# SFP.net
KiCad netlist of a schematic drawn in Altium Designer
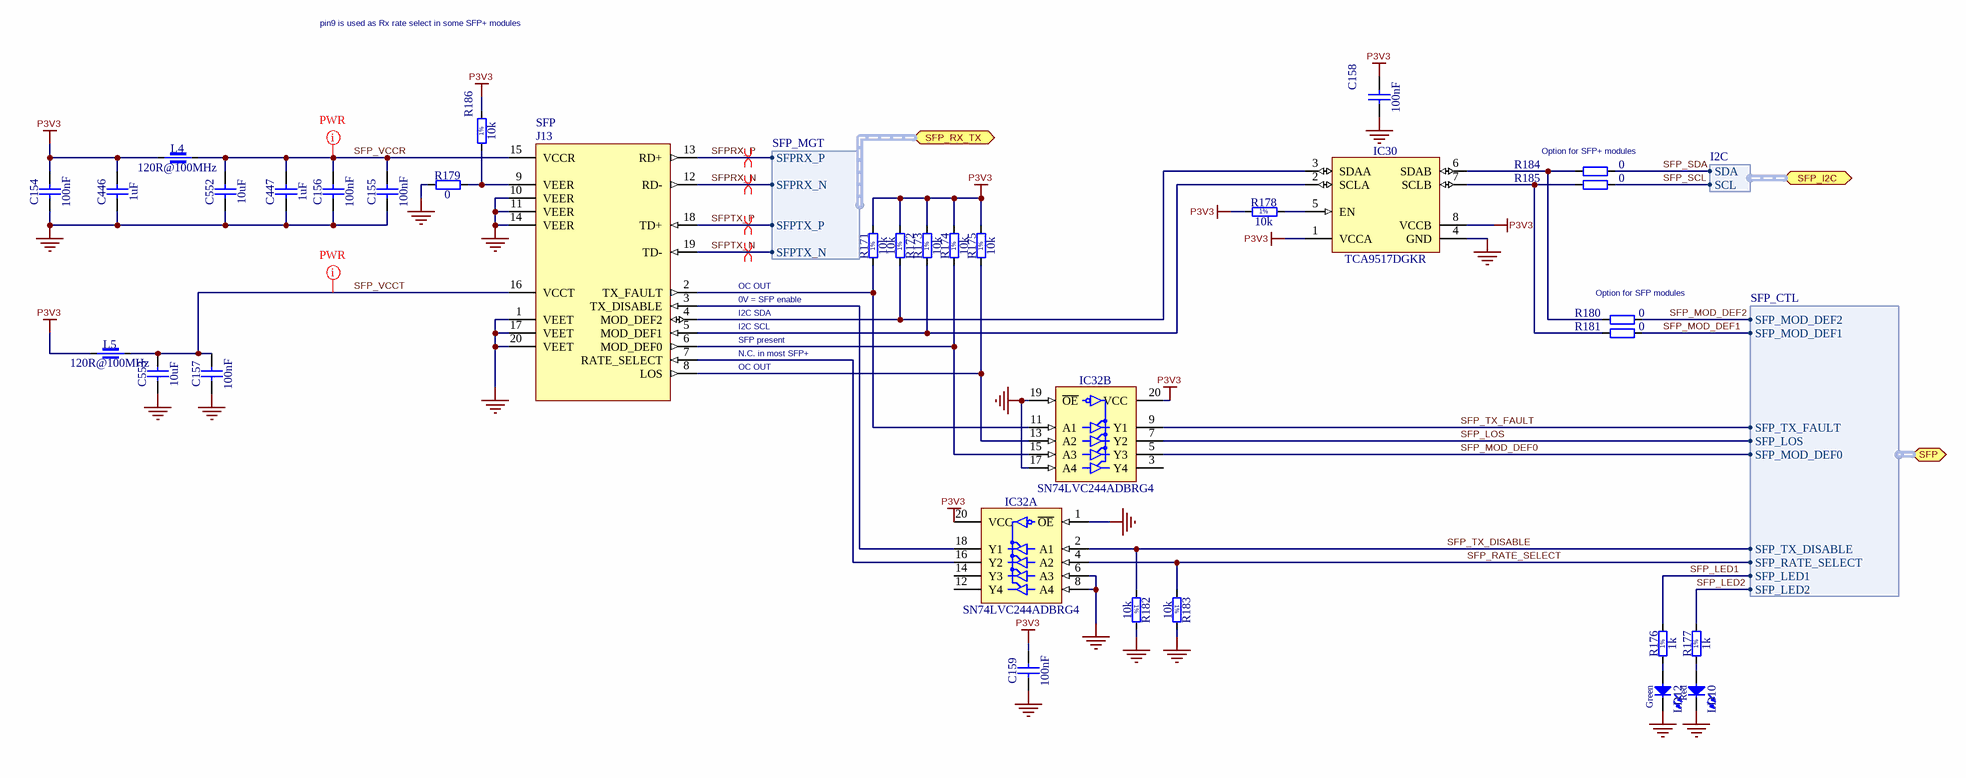
[diagram p0: SFP.SchDoc]

(export (version "E")
  (design (tool "Eeschema 10.0.6"))
  (components
    (comp (ref "C154")
      (value "100nF")
      (footprint "CAPC0603X33N")
      (description "Non-polarised capacitor")
      (fields
        (field (name "MANUFACTURER PART NUMBER") "CC0201_100NF_6.3V_10%_X5R")
        (field (name "MANUFACTURER") "GENERIC")
        (field (name "AUTHOR") "CERN DEM JLC")
      )
      (libsource (lib "Capacitors") (part "Capacitor - non polarized"))
    )
    (comp (ref "C155")
      (value "100nF")
      (footprint "CAPC0603X33N")
      (description "Non-polarised capacitor")
      (fields
        (field (name "MANUFACTURER PART NUMBER") "CC0201_100NF_6.3V_10%_X5R")
        (field (name "MANUFACTURER") "GENERIC")
        (field (name "AUTHOR") "CERN DEM JLC")
      )
      (libsource (lib "Capacitors") (part "Capacitor - non polarized"))
    )
    (comp (ref "C156")
      (value "100nF")
      (footprint "CAPC0603X33N")
      (description "Non-polarised capacitor")
      (fields
        (field (name "MANUFACTURER PART NUMBER") "CC0201_100NF_6.3V_10%_X5R")
        (field (name "MANUFACTURER") "GENERIC")
        (field (name "AUTHOR") "CERN DEM JLC")
      )
      (libsource (lib "Capacitors") (part "Capacitor - non polarized"))
    )
    (comp (ref "C157")
      (value "100nF")
      (footprint "CAPC0603X33N")
      (description "Non-polarised capacitor")
      (fields
        (field (name "MANUFACTURER PART NUMBER") "CC0201_100NF_6.3V_10%_X5R")
        (field (name "MANUFACTURER") "GENERIC")
        (field (name "AUTHOR") "CERN DEM JLC")
      )
      (libsource (lib "Capacitors") (part "Capacitor - non polarized"))
    )
    (comp (ref "C158")
      (value "100nF")
      (footprint "CAPC0603X33N")
      (description "Non-polarised capacitor")
      (fields
        (field (name "MANUFACTURER PART NUMBER") "CC0201_100NF_6.3V_10%_X5R")
        (field (name "MANUFACTURER") "GENERIC")
        (field (name "AUTHOR") "CERN DEM JLC")
      )
      (libsource (lib "Capacitors") (part "Capacitor - non polarized"))
    )
    (comp (ref "C159")
      (value "100nF")
      (footprint "CAPC0603X33N")
      (description "Non-polarised capacitor")
      (fields
        (field (name "MANUFACTURER PART NUMBER") "CC0201_100NF_6.3V_10%_X5R")
        (field (name "MANUFACTURER") "GENERIC")
        (field (name "AUTHOR") "CERN DEM JLC")
      )
      (libsource (lib "Capacitors") (part "Capacitor - non polarized"))
    )
    (comp (ref "C446")
      (value "1uF")
      (footprint "CAPC1005X55N")
      (description "Non-polarised capacitor")
      (fields
        (field (name "MANUFACTURER PART NUMBER") "CC0402_1UF_16V_10%_X5R")
        (field (name "MANUFACTURER") "GENERIC")
        (field (name "AUTHOR") "CERN DEM JLC")
      )
      (libsource (lib "Capacitors") (part "Capacitor - non polarized"))
    )
    (comp (ref "C447")
      (value "1uF")
      (footprint "CAPC1005X55N")
      (description "Non-polarised capacitor")
      (fields
        (field (name "MANUFACTURER PART NUMBER") "CC0402_1UF_16V_10%_X5R")
        (field (name "MANUFACTURER") "GENERIC")
        (field (name "AUTHOR") "CERN DEM JLC")
      )
      (libsource (lib "Capacitors") (part "Capacitor - non polarized"))
    )
    (comp (ref "C552")
      (value "10uF")
      (footprint "CAPC1608X87N")
      (description "Non-polarised capacitor")
      (fields
        (field (name "MANUFACTURER PART NUMBER") "CC0603_10uF_6.3V_20%_X5R")
        (field (name "MANUFACTURER") "GENERIC")
        (field (name "AUTHOR") "CERN DEM JLC")
      )
      (libsource (lib "Capacitors") (part "Capacitor - non polarized"))
    )
    (comp (ref "C553")
      (value "10uF")
      (footprint "CAPC1608X87N")
      (description "Non-polarised capacitor")
      (fields
        (field (name "MANUFACTURER PART NUMBER") "CC0603_10uF_6.3V_20%_X5R")
        (field (name "MANUFACTURER") "GENERIC")
        (field (name "AUTHOR") "CERN DEM JLC")
      )
      (libsource (lib "Capacitors") (part "Capacitor - non polarized"))
    )
    (comp (ref "IC30")
      (value "TCA9517DGKR")
      (footprint "SOP65P490X110-8N")
      (description "Level-Translating I2C Bus Repeater")
      (fields (field (name "MANUFACTURER") "TEXAS INSTRUMENTS") (field (name "AUTHOR") "CERN DEM JLC"))
      (libsource (lib "ICs And Semiconductors") (part "TCA9517"))
    )
    (comp (ref "IC32")
      (value "SN74LVC244ADBRG4")
      (footprint "SOP65P780X200-20N")
      (description "Octal Buffer/Driver with 3-State Ouputs")
      (fields (field (name "MANUFACTURER") "TEXAS INSTRUMENTS") (field (name "AUTHOR") "CERN DEM JMW"))
      (libsource (lib "ICs And Semiconductors") (part "74244_a"))
    )
    (comp (ref "J13")
      (value "SFP")
      (footprint "TYCO_1367073-1")
      (description "20 Position SFP  Connector (Small Form-factor Pluggable)")
      (fields
        (field (name "MANUFACTURER PART NUMBER") "1367073-1")
        (field (name "MANUFACTURER") "TYCO ELECTRONICS")
        (field (name "AUTHOR") "CERN DEM JLC")
      )
      (libsource (lib "Connectors") (part "SFPx1"))
    )
    (comp (ref "L4")
      (value "120R@100MHz")
      (footprint "INDC1608X65N")
      (fields
        (field (name "MANUFACTURER PART NUMBER") "BLM18SG121TN1D")
        (field (name "MANUFACTURER") "MURATA")
        (field (name "PART NUMBER") "IND0603_MURATA_BLM18SG121TN1D")
        (field (name "AUTHOR") "CERN DEM JLC")
      )
      (libsource (lib "Inductors & Transformers") (part "Ferrite Bead"))
    )
    (comp (ref "L5")
      (value "120R@100MHz")
      (footprint "INDC1608X65N")
      (fields
        (field (name "MANUFACTURER PART NUMBER") "BLM18SG121TN1D")
        (field (name "MANUFACTURER") "MURATA")
        (field (name "PART NUMBER") "IND0603_MURATA_BLM18SG121TN1D")
        (field (name "AUTHOR") "CERN DEM JLC")
      )
      (libsource (lib "Inductors & Transformers") (part "Ferrite Bead"))
    )
    (comp (ref "LD10")
      (value "Red")
      (footprint "LED_AVAGO_HSMC-C120")
      (description "LED Red 1C 2A")
      (fields
        (field (name "MANUFACTURER PART NUMBER") "HSMC-C120")
        (field (name "MANUFACTURER") "AVAGO TECHNOLOGIES")
        (field (name "AUTHOR") "CERN DEM JMW")
      )
      (libsource (lib "ICs And Semiconductors") (part "LED Red 1C 2A"))
    )
    (comp (ref "LD12")
      (value "Green")
      (footprint "LED_AVAGO_HSME-C120")
      (description "LED Green 1C 2A")
      (fields
        (field (name "MANUFACTURER PART NUMBER") "HSME-C120")
        (field (name "MANUFACTURER") "AVAGO TECHNOLOGIES")
        (field (name "AUTHOR") "CERN DEM JMW")
      )
      (libsource (lib "ICs And Semiconductors") (part "LED Green 1C 2A"))
    )
    (comp (ref "R171")
      (value "10k")
      (footprint "RESC1005X40N")
      (description "Resistor - 1%")
      (fields
        (field (name "MANUFACTURER PART NUMBER") "R0402_10K_1%_0.0625W_100PPM")
        (field (name "MANUFACTURER") "GENERIC")
        (field (name "AUTHOR") "CERN DEM JLC")
      )
      (libsource (lib "Resistors") (part "Resistor - 1%"))
    )
    (comp (ref "R172")
      (value "10k")
      (footprint "RESC1005X40N")
      (description "Resistor - 1%")
      (fields
        (field (name "MANUFACTURER PART NUMBER") "R0402_10K_1%_0.0625W_100PPM")
        (field (name "MANUFACTURER") "GENERIC")
        (field (name "AUTHOR") "CERN DEM JLC")
      )
      (libsource (lib "Resistors") (part "Resistor - 1%"))
    )
    (comp (ref "R173")
      (value "10k")
      (footprint "RESC1005X40N")
      (description "Resistor - 1%")
      (fields
        (field (name "MANUFACTURER PART NUMBER") "R0402_10K_1%_0.0625W_100PPM")
        (field (name "MANUFACTURER") "GENERIC")
        (field (name "AUTHOR") "CERN DEM JLC")
      )
      (libsource (lib "Resistors") (part "Resistor - 1%"))
    )
    (comp (ref "R174")
      (value "10k")
      (footprint "RESC1005X40N")
      (description "Resistor - 1%")
      (fields
        (field (name "MANUFACTURER PART NUMBER") "R0402_10K_1%_0.0625W_100PPM")
        (field (name "MANUFACTURER") "GENERIC")
        (field (name "AUTHOR") "CERN DEM JLC")
      )
      (libsource (lib "Resistors") (part "Resistor - 1%"))
    )
    (comp (ref "R175")
      (value "10k")
      (footprint "RESC1005X40N")
      (description "Resistor - 1%")
      (fields
        (field (name "MANUFACTURER PART NUMBER") "R0402_10K_1%_0.0625W_100PPM")
        (field (name "MANUFACTURER") "GENERIC")
        (field (name "AUTHOR") "CERN DEM JLC")
      )
      (libsource (lib "Resistors") (part "Resistor - 1%"))
    )
    (comp (ref "R176")
      (value "1k")
      (footprint "RESC1005X40N")
      (description "Resistor - 1%")
      (fields
        (field (name "MANUFACTURER PART NUMBER") "R0402_1K_1%_0.0625W_100PPM")
        (field (name "MANUFACTURER") "GENERIC")
        (field (name "AUTHOR") "CERN DEM JLC")
      )
      (libsource (lib "Resistors") (part "Resistor - 1%"))
    )
    (comp (ref "R177")
      (value "1k")
      (footprint "RESC1005X40N")
      (description "Resistor - 1%")
      (fields
        (field (name "MANUFACTURER PART NUMBER") "R0402_1K_1%_0.0625W_100PPM")
        (field (name "MANUFACTURER") "GENERIC")
        (field (name "AUTHOR") "CERN DEM JLC")
      )
      (libsource (lib "Resistors") (part "Resistor - 1%"))
    )
    (comp (ref "R178")
      (value "10k")
      (footprint "RESC1005X40N")
      (description "Resistor - 1%")
      (fields
        (field (name "MANUFACTURER PART NUMBER") "R0402_10K_1%_0.0625W_100PPM")
        (field (name "MANUFACTURER") "GENERIC")
        (field (name "AUTHOR") "CERN DEM JLC")
      )
      (libsource (lib "Resistors") (part "Resistor - 1%"))
    )
    (comp (ref "R179")
      (value "0")
      (footprint "RESC1005X40N")
      (description "Resistor")
      (fields
        (field (name "MANUFACTURER PART NUMBER") "R0402_0R_JUMPER")
        (field (name "MANUFACTURER") "GENERIC")
        (field (name "AUTHOR") "CERN DEM JLC")
      )
      (libsource (lib "Resistors") (part "Resistor"))
    )
    (comp (ref "R180")
      (value "0")
      (footprint "RESC1005X40N")
      (description "Resistor")
      (fields
        (field (name "MANUFACTURER PART NUMBER") "R0402_0R_JUMPER")
        (field (name "MANUFACTURER") "GENERIC")
        (field (name "AUTHOR") "CERN DEM JLC")
      )
      (libsource (lib "Resistors") (part "Resistor"))
    )
    (comp (ref "R181")
      (value "0")
      (footprint "RESC1005X40N")
      (description "Resistor")
      (fields
        (field (name "MANUFACTURER PART NUMBER") "R0402_0R_JUMPER")
        (field (name "MANUFACTURER") "GENERIC")
        (field (name "AUTHOR") "CERN DEM JLC")
      )
      (libsource (lib "Resistors") (part "Resistor"))
    )
    (comp (ref "R182")
      (value "10k")
      (footprint "RESC1005X40N")
      (description "Resistor - 1%")
      (fields
        (field (name "MANUFACTURER PART NUMBER") "R0402_10K_1%_0.0625W_100PPM")
        (field (name "MANUFACTURER") "GENERIC")
        (field (name "AUTHOR") "CERN DEM JLC")
      )
      (libsource (lib "Resistors") (part "Resistor - 1%"))
    )
    (comp (ref "R183")
      (value "10k")
      (footprint "RESC1005X40N")
      (description "Resistor - 1%")
      (fields
        (field (name "MANUFACTURER PART NUMBER") "R0402_10K_1%_0.0625W_100PPM")
        (field (name "MANUFACTURER") "GENERIC")
        (field (name "AUTHOR") "CERN DEM JLC")
      )
      (libsource (lib "Resistors") (part "Resistor - 1%"))
    )
    (comp (ref "R184")
      (value "0")
      (footprint "RESC1005X40N")
      (description "Resistor")
      (fields
        (field (name "MANUFACTURER PART NUMBER") "R0402_0R_JUMPER")
        (field (name "MANUFACTURER") "GENERIC")
        (field (name "AUTHOR") "CERN DEM JLC")
      )
      (libsource (lib "Resistors") (part "Resistor"))
    )
    (comp (ref "R185")
      (value "0")
      (footprint "RESC1005X40N")
      (description "Resistor")
      (fields
        (field (name "MANUFACTURER PART NUMBER") "R0402_0R_JUMPER")
        (field (name "MANUFACTURER") "GENERIC")
        (field (name "AUTHOR") "CERN DEM JLC")
      )
      (libsource (lib "Resistors") (part "Resistor"))
    )
    (comp (ref "R186")
      (value "10k")
      (footprint "RESC1005X40N")
      (description "Resistor - 1%")
      (fields
        (field (name "MANUFACTURER PART NUMBER") "R0402_10K_1%_0.0625W_100PPM")
        (field (name "MANUFACTURER") "GENERIC")
        (field (name "AUTHOR") "CERN DEM JLC")
      )
      (libsource (lib "Resistors") (part "Resistor - 1%"))
    )
  )
  (nets
    (net (code "4") (name "/SFPRX_N") (class "Default")
      (node (ref "J13") (pin "12") (pinfunction "RD-_12") (pintype "output"))
    )
    (net (code "5") (name "/SFPRX_P") (class "Default")
      (node (ref "J13") (pin "13") (pinfunction "RD+_13") (pintype "output"))
    )
    (net (code "6") (name "/SFPTX_N") (class "Default")
      (node (ref "J13") (pin "19") (pinfunction "TD-_19") (pintype "input"))
    )
    (net (code "7") (name "/SFPTX_P") (class "Default")
      (node (ref "J13") (pin "18") (pinfunction "TD+_18") (pintype "input"))
    )
    (net (code "8") (name "/SFP_LED1") (class "Default")
      (node (ref "R176") (pin "2") (pinfunction "2_2") (pintype "passive"))
    )
    (net (code "9") (name "/SFP_LED2") (class "Default")
      (node (ref "R177") (pin "2") (pinfunction "2_2") (pintype "passive"))
    )
    (net (code "10") (name "/SFP_LOS") (class "Default")
      (node (ref "IC32") (pin "7") (pinfunction "Y2_7") (pintype "tri_state"))
    )
    (net (code "11") (name "/SFP_MOD_DEF0") (class "Default")
      (node (ref "IC32") (pin "5") (pinfunction "Y3_5") (pintype "tri_state"))
    )
    (net (code "12") (name "/SFP_MOD_DEF1") (class "Default")
      (node (ref "R181") (pin "2") (pinfunction "2_2") (pintype "passive"))
    )
    (net (code "13") (name "/SFP_MOD_DEF2") (class "Default")
      (node (ref "R180") (pin "2") (pinfunction "2_2") (pintype "passive"))
    )
    (net (code "14") (name "/SFP_RATE_SELECT") (class "Default")
      (node (ref "IC32") (pin "4") (pinfunction "A2_4") (pintype "input"))
      (node (ref "R183") (pin "1") (pinfunction "1_1") (pintype "passive"))
    )
    (net (code "15") (name "/SFP_SCL") (class "Default")
      (node (ref "R185") (pin "2") (pinfunction "2_2") (pintype "passive"))
    )
    (net (code "16") (name "/SFP_SDA") (class "Default")
      (node (ref "R184") (pin "2") (pinfunction "2_2") (pintype "passive"))
    )
    (net (code "17") (name "/SFP_TX_DISABLE") (class "Default")
      (node (ref "IC32") (pin "2") (pinfunction "A1_2") (pintype "input"))
      (node (ref "R182") (pin "1") (pinfunction "1_1") (pintype "passive"))
    )
    (net (code "18") (name "/SFP_TX_FAULT") (class "Default")
      (node (ref "IC32") (pin "9") (pinfunction "Y1_9") (pintype "tri_state"))
    )
    (net (code "19") (name "/SFP_VCCR") (class "Default")
      (node (ref "C155") (pin "2") (pinfunction "2_2") (pintype "passive"))
      (node (ref "C156") (pin "2") (pinfunction "2_2") (pintype "passive"))
      (node (ref "C447") (pin "2") (pinfunction "2_2") (pintype "passive"))
      (node (ref "C552") (pin "2") (pinfunction "2_2") (pintype "passive"))
      (node (ref "J13") (pin "15") (pinfunction "VCCR_15") (pintype "power_in"))
      (node (ref "L4") (pin "2") (pinfunction "2_2") (pintype "passive"))
    )
    (net (code "20") (name "/SFP_VCCT") (class "Default")
      (node (ref "C157") (pin "2") (pinfunction "2_2") (pintype "passive"))
      (node (ref "C553") (pin "2") (pinfunction "2_2") (pintype "passive"))
      (node (ref "J13") (pin "16") (pinfunction "VCCT_16") (pintype "power_in"))
      (node (ref "L5") (pin "2") (pinfunction "2_2") (pintype "passive"))
    )
    (net (code "24") (name "GND") (class "Default")
      (node (ref "C154") (pin "1") (pinfunction "1_1") (pintype "passive"))
      (node (ref "C155") (pin "1") (pinfunction "1_1") (pintype "passive"))
      (node (ref "C156") (pin "1") (pinfunction "1_1") (pintype "passive"))
      (node (ref "C157") (pin "1") (pinfunction "1_1") (pintype "passive"))
      (node (ref "C158") (pin "1") (pinfunction "1_1") (pintype "passive"))
      (node (ref "C159") (pin "1") (pinfunction "1_1") (pintype "passive"))
      (node (ref "C446") (pin "1") (pinfunction "1_1") (pintype "passive"))
      (node (ref "C447") (pin "1") (pinfunction "1_1") (pintype "passive"))
      (node (ref "C552") (pin "1") (pinfunction "1_1") (pintype "passive"))
      (node (ref "C553") (pin "1") (pinfunction "1_1") (pintype "passive"))
      (node (ref "IC30") (pin "4") (pinfunction "GND_4") (pintype "power_in"))
      (node (ref "IC32") (pin "1") (pinfunction "~{OE}_1") (pintype "input"))
      (node (ref "IC32") (pin "10") (pinfunction "GND_10") (pintype "power_in"))
      (node (ref "IC32") (pin "17") (pinfunction "A4_17") (pintype "input"))
      (node (ref "IC32") (pin "19") (pinfunction "~{OE}_19") (pintype "input"))
      (node (ref "IC32") (pin "6") (pinfunction "A3_6") (pintype "input"))
      (node (ref "IC32") (pin "8") (pinfunction "A4_8") (pintype "input"))
      (node (ref "J13") (pin "1") (pinfunction "VEET_1") (pintype "power_in"))
      (node (ref "J13") (pin "10") (pinfunction "VEER_10") (pintype "power_in"))
      (node (ref "J13") (pin "11") (pinfunction "VEER_11") (pintype "power_in"))
      (node (ref "J13") (pin "14") (pinfunction "VEER_14") (pintype "power_in"))
      (node (ref "J13") (pin "17") (pinfunction "VEET_17") (pintype "power_in"))
      (node (ref "J13") (pin "20") (pinfunction "VEET_20") (pintype "power_in"))
      (node (ref "LD10") (pin "1") (pinfunction "C_1") (pintype "passive"))
      (node (ref "LD12") (pin "1") (pinfunction "C_1") (pintype "passive"))
      (node (ref "R179") (pin "1") (pinfunction "1_1") (pintype "passive"))
      (node (ref "R182") (pin "2") (pinfunction "2_2") (pintype "passive"))
      (node (ref "R183") (pin "2") (pinfunction "2_2") (pintype "passive"))
    )
    (net (code "25") (name "Net-(IC30-EN)") (class "Default")
      (node (ref "IC30") (pin "5") (pinfunction "EN_5") (pintype "input"))
      (node (ref "R178") (pin "2") (pinfunction "2_2") (pintype "passive"))
    )
    (net (code "26") (name "Net-(IC30-SCLA)") (class "Default")
      (node (ref "IC30") (pin "2") (pinfunction "SCLA_2") (pintype "bidirectional"))
      (node (ref "J13") (pin "5") (pinfunction "MOD_DEF1_5") (pintype "input"))
      (node (ref "R173") (pin "1") (pinfunction "1_1") (pintype "passive"))
    )
    (net (code "27") (name "Net-(IC30-SCLB)") (class "Default")
      (node (ref "IC30") (pin "7") (pinfunction "SCLB_7") (pintype "bidirectional"))
      (node (ref "R181") (pin "1") (pinfunction "1_1") (pintype "passive"))
      (node (ref "R185") (pin "1") (pinfunction "1_1") (pintype "passive"))
    )
    (net (code "28") (name "Net-(IC30-SDAA)") (class "Default")
      (node (ref "IC30") (pin "3") (pinfunction "SDAA_3") (pintype "bidirectional"))
      (node (ref "J13") (pin "4") (pinfunction "MOD_DEF2_4") (pintype "bidirectional"))
      (node (ref "R172") (pin "1") (pinfunction "1_1") (pintype "passive"))
    )
    (net (code "29") (name "Net-(IC30-SDAB)") (class "Default")
      (node (ref "IC30") (pin "6") (pinfunction "SDAB_6") (pintype "bidirectional"))
      (node (ref "R180") (pin "1") (pinfunction "1_1") (pintype "passive"))
      (node (ref "R184") (pin "1") (pinfunction "1_1") (pintype "passive"))
    )
    (net (code "30") (name "Net-(IC32A-Y1)") (class "Default")
      (node (ref "IC32") (pin "18") (pinfunction "Y1_18") (pintype "tri_state"))
      (node (ref "J13") (pin "3") (pinfunction "TX_DISABLE_3") (pintype "input"))
    )
    (net (code "31") (name "Net-(IC32A-Y2)") (class "Default")
      (node (ref "IC32") (pin "16") (pinfunction "Y2_16") (pintype "tri_state"))
      (node (ref "J13") (pin "7") (pinfunction "RATE_SELECT_7") (pintype "input"))
    )
    (net (code "32") (name "Net-(IC32B-A1)") (class "Default")
      (node (ref "IC32") (pin "11") (pinfunction "A1_11") (pintype "input"))
      (node (ref "J13") (pin "2") (pinfunction "TX_FAULT_2") (pintype "output"))
      (node (ref "R171") (pin "1") (pinfunction "1_1") (pintype "passive"))
    )
    (net (code "33") (name "Net-(IC32B-A2)") (class "Default")
      (node (ref "IC32") (pin "13") (pinfunction "A2_13") (pintype "input"))
      (node (ref "J13") (pin "8") (pinfunction "LOS_8") (pintype "output"))
      (node (ref "R175") (pin "1") (pinfunction "1_1") (pintype "passive"))
    )
    (net (code "34") (name "Net-(IC32B-A3)") (class "Default")
      (node (ref "IC32") (pin "15") (pinfunction "A3_15") (pintype "input"))
      (node (ref "J13") (pin "6") (pinfunction "MOD_DEF0_6") (pintype "output"))
      (node (ref "R174") (pin "1") (pinfunction "1_1") (pintype "passive"))
    )
    (net (code "35") (name "Net-(J13-VEER-Pad9)") (class "Default")
      (node (ref "J13") (pin "9") (pinfunction "VEER_9") (pintype "power_in"))
      (node (ref "R179") (pin "2") (pinfunction "2_2") (pintype "passive"))
      (node (ref "R186") (pin "1") (pinfunction "1_1") (pintype "passive"))
    )
    (net (code "36") (name "Net-(LD10-A)") (class "Default")
      (node (ref "LD10") (pin "2") (pinfunction "A_2") (pintype "passive"))
      (node (ref "R177") (pin "1") (pinfunction "1_1") (pintype "passive"))
    )
    (net (code "37") (name "Net-(LD12-A)") (class "Default")
      (node (ref "LD12") (pin "2") (pinfunction "A_2") (pintype "passive"))
      (node (ref "R176") (pin "1") (pinfunction "1_1") (pintype "passive"))
    )
    (net (code "38") (name "P3V3") (class "Default")
      (node (ref "C154") (pin "2") (pinfunction "2_2") (pintype "passive"))
      (node (ref "C158") (pin "2") (pinfunction "2_2") (pintype "passive"))
      (node (ref "C159") (pin "2") (pinfunction "2_2") (pintype "passive"))
      (node (ref "C446") (pin "2") (pinfunction "2_2") (pintype "passive"))
      (node (ref "IC30") (pin "1") (pinfunction "VCCA_1") (pintype "power_in"))
      (node (ref "IC30") (pin "8") (pinfunction "VCCB_8") (pintype "power_in"))
      (node (ref "IC32") (pin "20") (pinfunction "VCC_20") (pintype "power_in"))
      (node (ref "L4") (pin "1") (pinfunction "1_1") (pintype "passive"))
      (node (ref "L5") (pin "1") (pinfunction "1_1") (pintype "passive"))
      (node (ref "R171") (pin "2") (pinfunction "2_2") (pintype "passive"))
      (node (ref "R172") (pin "2") (pinfunction "2_2") (pintype "passive"))
      (node (ref "R173") (pin "2") (pinfunction "2_2") (pintype "passive"))
      (node (ref "R174") (pin "2") (pinfunction "2_2") (pintype "passive"))
      (node (ref "R175") (pin "2") (pinfunction "2_2") (pintype "passive"))
      (node (ref "R178") (pin "1") (pinfunction "1_1") (pintype "passive"))
      (node (ref "R186") (pin "2") (pinfunction "2_2") (pintype "passive"))
    )
    (net (code "39") (name "unconnected-(IC32A-Y3-Pad14)") (class "Default")
      (node (ref "IC32") (pin "14") (pinfunction "Y3_14") (pintype "tri_state"))
    )
    (net (code "40") (name "unconnected-(IC32A-Y4-Pad12)") (class "Default")
      (node (ref "IC32") (pin "12") (pinfunction "Y4_12") (pintype "tri_state"))
    )
    (net (code "41") (name "unconnected-(IC32B-Y4-Pad3)") (class "Default")
      (node (ref "IC32") (pin "3") (pinfunction "Y4_3") (pintype "tri_state"))
    )
  )
)
